# LDO_3v3_LM2937.net
KiCad netlist of a schematic drawn in Altium Designer
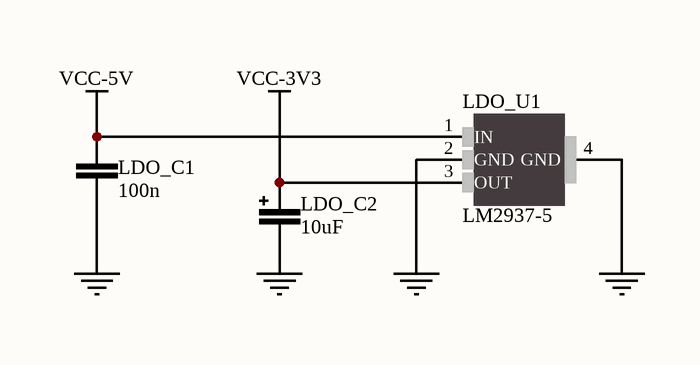
[diagram p0: LDO_3v3_LM2937.SchDoc]

(export (version "E")
  (design (tool "Eeschema 10.0.6"))
  (components
    (comp (ref "LDO_C1")
      (value "100n")
      (footprint "CER_0603")
      (description "CAP CER 100n 10V X5R 10% 0603")
      (libsource (lib "Capacitors") (part "06032105"))
    )
    (comp (ref "LDO_C2")
      (value "10uF")
      (footprint "TANT_1210")
      (description "CAP TANT 10u")
      (libsource (lib "Capacitors") (part "00001106"))
    )
    (comp (ref "LDO_U1")
      (value "LM2937-5")
      (footprint "SOT223")
      (description "IC REG LINEAR 5V 400MA SOT223-4")
      (libsource (lib "Integrated_circuits") (part "LM2937"))
    )
  )
  (nets
    (net (code "1") (name "GND") (class "Default")
      (node (ref "LDO_C1") (pin "1") (pinfunction "1_1") (pintype "passive"))
      (node (ref "LDO_C2") (pin "2") (pinfunction "2_2") (pintype "passive"))
      (node (ref "LDO_U1") (pin "2") (pinfunction "GND_2") (pintype "passive"))
      (node (ref "LDO_U1") (pin "4") (pinfunction "GND_4") (pintype "passive"))
    )
    (net (code "2") (name "VCC-3V3") (class "Default")
      (node (ref "LDO_C2") (pin "1") (pinfunction "1_1") (pintype "passive"))
      (node (ref "LDO_U1") (pin "3") (pinfunction "OUT_3") (pintype "passive"))
    )
    (net (code "3") (name "VCC-5V") (class "Default")
      (node (ref "LDO_C1") (pin "2") (pinfunction "2_2") (pintype "passive"))
      (node (ref "LDO_U1") (pin "1") (pinfunction "IN_1") (pintype "passive"))
    )
  )
)
